# PowerBoard.net
KiCad netlist of a schematic drawn in EAGLE
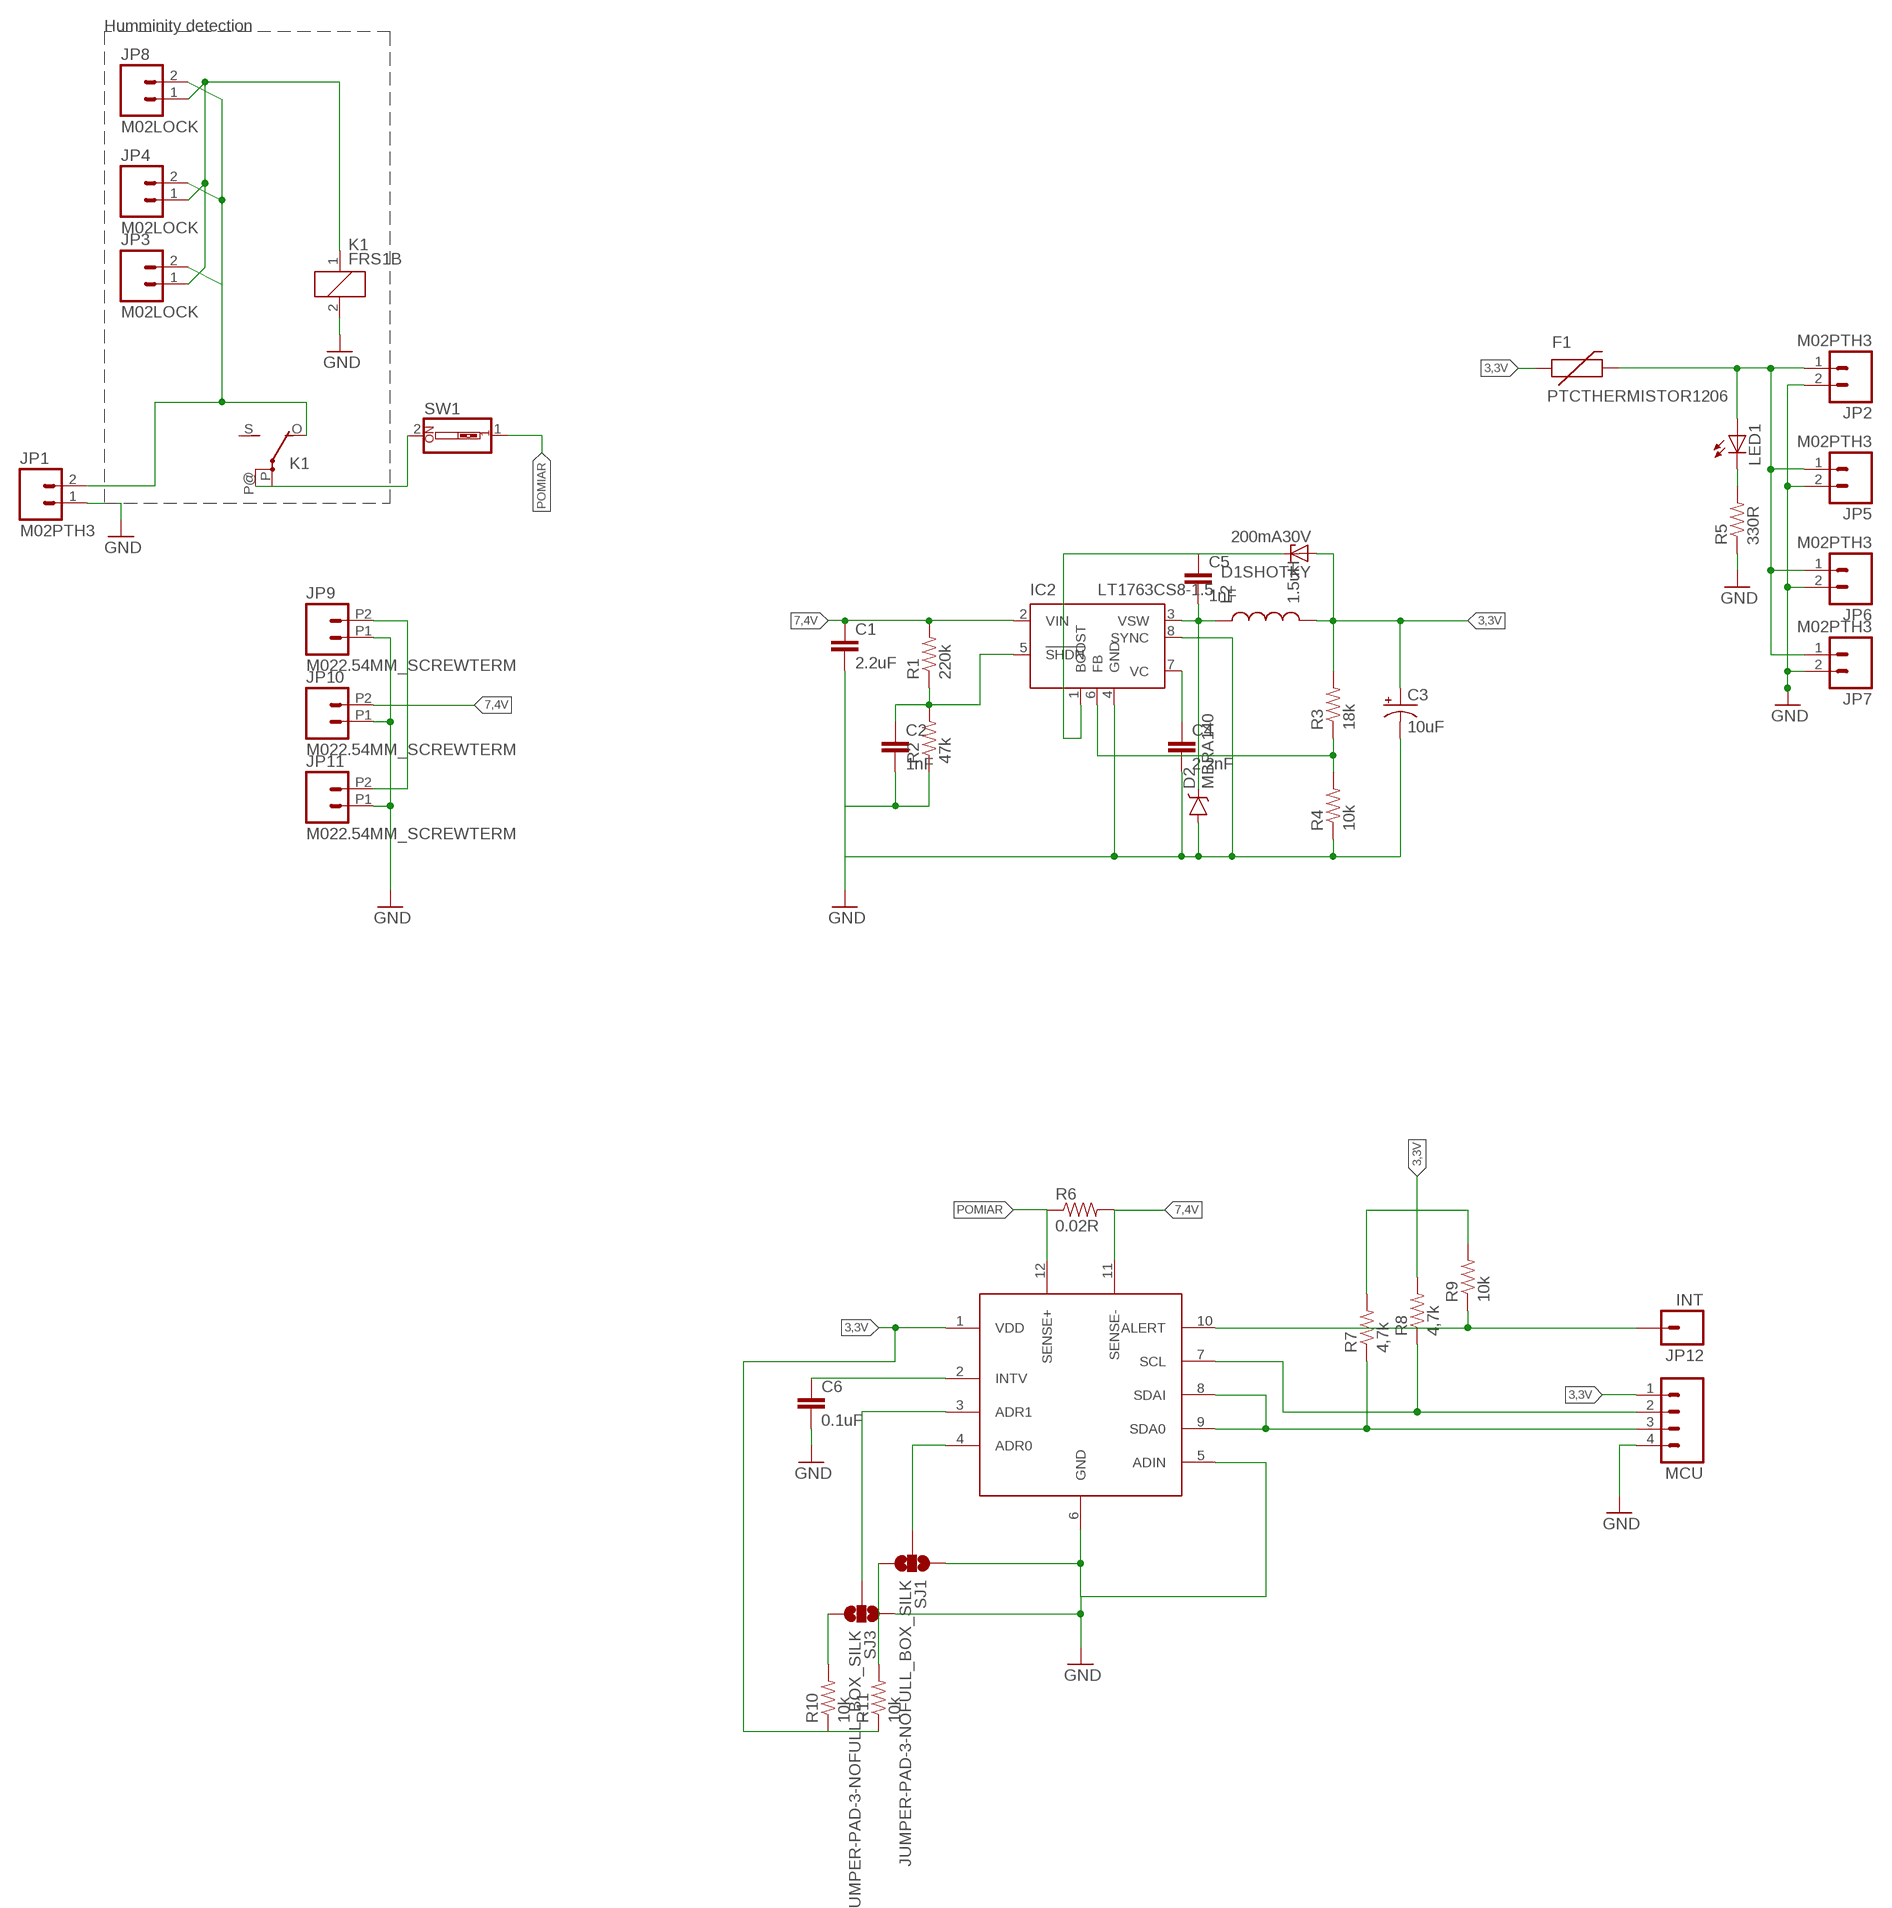
[diagram p0: schematic, sheet 1]

(export (version "E")
  (design (tool "Eeschema 10.0.6"))
  (components
    (comp (ref "C1")
      (value "2.2uF")
      (footprint "eagle-import:0805")
      (libsource (lib "eagle-import") (part "CAP0805"))
    )
    (comp (ref "C2")
      (value "1nF")
      (footprint "eagle-import:0805")
      (libsource (lib "eagle-import") (part "CAP0805"))
    )
    (comp (ref "C3")
      (value "10uF")
      (footprint "eagle-import:PANASONIC_C")
      (libsource (lib "eagle-import") (part "CAP_POLC"))
    )
    (comp (ref "C4")
      (value "2.2nF")
      (footprint "eagle-import:0805")
      (libsource (lib "eagle-import") (part "CAP0805"))
    )
    (comp (ref "C5")
      (value "1nF")
      (footprint "eagle-import:0805")
      (libsource (lib "eagle-import") (part "CAP0805"))
    )
    (comp (ref "C6")
      (value "0.1uF")
      (footprint "eagle-import:0805")
      (libsource (lib "eagle-import") (part "CAP0805"))
    )
    (comp (ref "D1SHOTKY")
      (value "200mA30V")
      (footprint "eagle-import:SOD80C")
      (libsource (lib "eagle-import") (part "ZENER-DIODESOD80C"))
    )
    (comp (ref "D2")
      (value "MBRA140")
      (footprint "eagle-import:SMA-DIODE")
      (libsource (lib "eagle-import") (part "MBRA140"))
    )
    (comp (ref "F1")
      (value "PTCTHERMISTOR1206")
      (footprint "eagle-import:PTC-1206")
      (libsource (lib "eagle-import") (part "PTCTHERMISTOR1206"))
    )
    (comp (ref "IC2")
      (value "LT1763CS8-1.5")
      (footprint "eagle-import:SOIC8")
      (libsource (lib "eagle-import") (part "LT1763CS8-1.5"))
    )
    (comp (ref "JP1")
      (value "M02PTH3")
      (footprint "eagle-import:1X02_LONGPADS")
      (libsource (lib "eagle-import") (part "M02PTH3"))
    )
    (comp (ref "JP2")
      (value "M02PTH3")
      (footprint "eagle-import:1X02_LONGPADS")
      (libsource (lib "eagle-import") (part "M02PTH3"))
    )
    (comp (ref "JP3")
      (value "M02LOCK")
      (footprint "eagle-import:1X02_LOCK")
      (libsource (lib "eagle-import") (part "M02LOCK"))
    )
    (comp (ref "JP4")
      (value "M02LOCK")
      (footprint "eagle-import:1X02_LOCK")
      (libsource (lib "eagle-import") (part "M02LOCK"))
    )
    (comp (ref "JP5")
      (value "M02PTH3")
      (footprint "eagle-import:1X02_LONGPADS")
      (libsource (lib "eagle-import") (part "M02PTH3"))
    )
    (comp (ref "JP6")
      (value "M02PTH3")
      (footprint "eagle-import:1X02_LONGPADS")
      (libsource (lib "eagle-import") (part "M02PTH3"))
    )
    (comp (ref "JP7")
      (value "M02PTH3")
      (footprint "eagle-import:1X02_LONGPADS")
      (libsource (lib "eagle-import") (part "M02PTH3"))
    )
    (comp (ref "JP8")
      (value "M02LOCK")
      (footprint "eagle-import:1X02_LOCK")
      (libsource (lib "eagle-import") (part "M02LOCK"))
    )
    (comp (ref "JP9")
      (value "M022.54MM_SCREWTERM")
      (footprint "eagle-import:1X02_2.54_SCREWTERM")
      (libsource (lib "eagle-import") (part "M022.54MM_SCREWTERM"))
    )
    (comp (ref "JP10")
      (value "M022.54MM_SCREWTERM")
      (footprint "eagle-import:1X02_2.54_SCREWTERM")
      (libsource (lib "eagle-import") (part "M022.54MM_SCREWTERM"))
    )
    (comp (ref "JP11")
      (value "M022.54MM_SCREWTERM")
      (footprint "eagle-import:1X02_2.54_SCREWTERM")
      (libsource (lib "eagle-import") (part "M022.54MM_SCREWTERM"))
    )
    (comp (ref "JP12")
      (value "INT")
      (footprint "eagle-import:1X01_LONGPAD")
      (libsource (lib "eagle-import") (part "M01PTH_LONGPAD"))
    )
    (comp (ref "K1")
      (value "FRS1B")
      (footprint "eagle-import:FRS1B")
      (libsource (lib "eagle-import") (part "FRS1B"))
    )
    (comp (ref "L2")
      (value "1.5uH")
      (footprint "eagle-import:B82462G")
      (libsource (lib "eagle-import") (part "INDUCTOR-B82462G"))
    )
    (comp (ref "LED1")
      (value "LEDSML0805")
      (footprint "eagle-import:SML0805")
      (libsource (lib "eagle-import") (part "LEDSML0805"))
    )
    (comp (ref "MCU")
      (value "M04POLAR_LOCK")
      (footprint "eagle-import:MOLEX-1X4_LOCK")
      (libsource (lib "eagle-import") (part "M04POLAR_LOCK"))
    )
    (comp (ref "R1")
      (value "220k")
      (footprint "eagle-import:0805")
      (libsource (lib "eagle-import") (part "SparkFun-Resistors_RESISTOR0805-RES"))
    )
    (comp (ref "R2")
      (value "47k")
      (footprint "eagle-import:0805")
      (libsource (lib "eagle-import") (part "SparkFun-Resistors_RESISTOR0805-RES"))
    )
    (comp (ref "R3")
      (value "18k")
      (footprint "eagle-import:0805")
      (libsource (lib "eagle-import") (part "SparkFun-Resistors_RESISTOR0805-RES"))
    )
    (comp (ref "R4")
      (value "10k")
      (footprint "eagle-import:0805")
      (libsource (lib "eagle-import") (part "SparkFun-Resistors_RESISTOR0805-RES"))
    )
    (comp (ref "R5")
      (value "330R")
      (footprint "eagle-import:0805")
      (libsource (lib "eagle-import") (part "SparkFun-Resistors_RESISTOR0805-RES"))
    )
    (comp (ref "R6")
      (value "0.02R")
      (footprint "eagle-import:R2512")
      (libsource (lib "eagle-import") (part "RESISTOR2512"))
    )
    (comp (ref "R7")
      (value "4,7k")
      (footprint "eagle-import:0805")
      (libsource (lib "eagle-import") (part "SparkFun-Resistors_RESISTOR0805-RES"))
    )
    (comp (ref "R8")
      (value "4,7k")
      (footprint "eagle-import:0805")
      (libsource (lib "eagle-import") (part "SparkFun-Resistors_RESISTOR0805-RES"))
    )
    (comp (ref "R9")
      (value "10k")
      (footprint "eagle-import:0805")
      (libsource (lib "eagle-import") (part "SparkFun-Resistors_RESISTOR0805-RES"))
    )
    (comp (ref "R10")
      (value "10k")
      (footprint "eagle-import:0805")
      (libsource (lib "eagle-import") (part "SparkFun-Resistors_RESISTOR0805-RES"))
    )
    (comp (ref "R11")
      (value "10k")
      (footprint "eagle-import:0805")
      (libsource (lib "eagle-import") (part "SparkFun-Resistors_RESISTOR0805-RES"))
    )
    (comp (ref "SJ1")
      (value "JUMPER-PAD-3-NOFULL_BOX_SILK")
      (footprint "eagle-import:PAD-JUMPER-3-NO_YES_SILK_FULL_BOX")
      (libsource (lib "eagle-import") (part "JUMPER-PAD-3-NOFULL_BOX_SILK"))
    )
    (comp (ref "SJ3")
      (value "JUMPER-PAD-3-NOFULL_BOX_SILK")
      (footprint "eagle-import:PAD-JUMPER-3-NO_YES_SILK_FULL_BOX")
      (libsource (lib "eagle-import") (part "JUMPER-PAD-3-NOFULL_BOX_SILK"))
    )
    (comp (ref "SW1")
      (value "SW_DIP-1")
      (footprint "eagle-import:EDG-01")
      (libsource (lib "eagle-import") (part "SW_DIP-1"))
    )
    (comp (ref "U$1")
      (value "LTC2945")
      (footprint "eagle-import:SOP65P490X110-12N")
      (libsource (lib "eagle-import") (part "LTC2945"))
    )
  )
  (nets
    (net (code "1") (name "3,3V") (class "Default")
      (node (ref "C3") (pin "+") (pinfunction "+_+") (pintype "passive"))
      (node (ref "D1SHOTKY") (pin "A") (pinfunction "A_A") (pintype "passive"))
      (node (ref "F1") (pin "1") (pinfunction "1_1") (pintype "bidirectional"))
      (node (ref "L2") (pin "P$2") (pinfunction "2_P$2") (pintype "passive"))
      (node (ref "MCU") (pin "1") (pinfunction "1_1") (pintype "passive"))
      (node (ref "R10") (pin "1") (pinfunction "1_1") (pintype "passive"))
      (node (ref "R11") (pin "1") (pinfunction "1_1") (pintype "passive"))
      (node (ref "R3") (pin "2") (pinfunction "2_2") (pintype "passive"))
      (node (ref "R7") (pin "2") (pinfunction "2_2") (pintype "passive"))
      (node (ref "R8") (pin "2") (pinfunction "2_2") (pintype "passive"))
      (node (ref "R9") (pin "2") (pinfunction "2_2") (pintype "passive"))
      (node (ref "U$1") (pin "1") (pinfunction "VDD_1") (pintype "bidirectional"))
    )
    (net (code "2") (name "7,4V") (class "Default")
      (node (ref "C1") (pin "1") (pinfunction "1_1") (pintype "passive"))
      (node (ref "IC2") (pin "2") (pinfunction "VIN_2") (pintype "input"))
      (node (ref "JP10") (pin "P2") (pinfunction "2_P2") (pintype "passive"))
      (node (ref "JP11") (pin "P2") (pinfunction "2_P2") (pintype "passive"))
      (node (ref "JP9") (pin "P2") (pinfunction "2_P2") (pintype "passive"))
      (node (ref "R1") (pin "2") (pinfunction "2_2") (pintype "passive"))
      (node (ref "R6") (pin "2") (pinfunction "2_2") (pintype "passive"))
      (node (ref "U$1") (pin "11") (pinfunction "SENSE-_11") (pintype "bidirectional"))
    )
    (net (code "3") (name "GND") (class "Default")
      (node (ref "C1") (pin "2") (pinfunction "2_2") (pintype "passive"))
      (node (ref "C2") (pin "2") (pinfunction "2_2") (pintype "passive"))
      (node (ref "C3") (pin "-") (pinfunction "-_-") (pintype "passive"))
      (node (ref "C4") (pin "2") (pinfunction "2_2") (pintype "passive"))
      (node (ref "C6") (pin "2") (pinfunction "2_2") (pintype "passive"))
      (node (ref "D2") (pin "A") (pinfunction "A_A") (pintype "passive"))
      (node (ref "IC2") (pin "4") (pinfunction "GND_4") (pintype "power_in"))
      (node (ref "IC2") (pin "8") (pinfunction "SYNC_8") (pintype "input"))
      (node (ref "JP1") (pin "1") (pinfunction "1_1") (pintype "passive"))
      (node (ref "JP10") (pin "P1") (pinfunction "1_P1") (pintype "passive"))
      (node (ref "JP11") (pin "P1") (pinfunction "1_P1") (pintype "passive"))
      (node (ref "JP2") (pin "2") (pinfunction "2_2") (pintype "passive"))
      (node (ref "JP5") (pin "2") (pinfunction "2_2") (pintype "passive"))
      (node (ref "JP6") (pin "2") (pinfunction "2_2") (pintype "passive"))
      (node (ref "JP7") (pin "2") (pinfunction "2_2") (pintype "passive"))
      (node (ref "JP9") (pin "P1") (pinfunction "1_P1") (pintype "passive"))
      (node (ref "K1") (pin "2") (pinfunction "2_2") (pintype "passive"))
      (node (ref "MCU") (pin "4") (pinfunction "4_4") (pintype "passive"))
      (node (ref "R2") (pin "1") (pinfunction "1_1") (pintype "passive"))
      (node (ref "R4") (pin "1") (pinfunction "1_1") (pintype "passive"))
      (node (ref "R5") (pin "1") (pinfunction "1_1") (pintype "passive"))
      (node (ref "SJ1") (pin "1") (pinfunction "1_1") (pintype "passive"))
      (node (ref "SJ3") (pin "1") (pinfunction "1_1") (pintype "passive"))
      (node (ref "U$1") (pin "5") (pinfunction "ADIN_5") (pintype "bidirectional"))
      (node (ref "U$1") (pin "6") (pinfunction "GND_6") (pintype "bidirectional"))
    )
    (net (code "4") (name "Net-(F1-Pad2)") (class "Default")
      (node (ref "F1") (pin "2") (pinfunction "2_2") (pintype "bidirectional"))
      (node (ref "JP2") (pin "1") (pinfunction "1_1") (pintype "passive"))
      (node (ref "JP5") (pin "1") (pinfunction "1_1") (pintype "passive"))
      (node (ref "JP6") (pin "1") (pinfunction "1_1") (pintype "passive"))
      (node (ref "JP7") (pin "1") (pinfunction "1_1") (pintype "passive"))
      (node (ref "LED1") (pin "A") (pinfunction "A_A") (pintype "passive"))
    )
    (net (code "5") (name "Net-(IC2-BOOST)") (class "Default")
      (node (ref "C5") (pin "1") (pinfunction "1_1") (pintype "passive"))
      (node (ref "D1SHOTKY") (pin "C") (pinfunction "C_C") (pintype "passive"))
      (node (ref "IC2") (pin "1") (pinfunction "BOOST_1") (pintype "power_in"))
    )
    (net (code "6") (name "Net-(IC2-FB)") (class "Default")
      (node (ref "IC2") (pin "6") (pinfunction "FB_6") (pintype "power_in"))
      (node (ref "R3") (pin "1") (pinfunction "1_1") (pintype "passive"))
      (node (ref "R4") (pin "2") (pinfunction "2_2") (pintype "passive"))
    )
    (net (code "7") (name "Net-(IC2-VC)") (class "Default")
      (node (ref "C4") (pin "1") (pinfunction "1_1") (pintype "passive"))
      (node (ref "IC2") (pin "7") (pinfunction "VC_7") (pintype "input"))
    )
    (net (code "8") (name "Net-(IC2-VSW)") (class "Default")
      (node (ref "C5") (pin "2") (pinfunction "2_2") (pintype "passive"))
      (node (ref "D2") (pin "C") (pinfunction "C_C") (pintype "passive"))
      (node (ref "IC2") (pin "3") (pinfunction "VSW_3") (pintype "passive"))
      (node (ref "L2") (pin "P$1") (pinfunction "1_P$1") (pintype "passive"))
    )
    (net (code "9") (name "Net-(IC2-~{SHDN})") (class "Default")
      (node (ref "C2") (pin "1") (pinfunction "1_1") (pintype "passive"))
      (node (ref "IC2") (pin "5") (pinfunction "~{SHDN}_5") (pintype "input"))
      (node (ref "R1") (pin "1") (pinfunction "1_1") (pintype "passive"))
      (node (ref "R2") (pin "2") (pinfunction "2_2") (pintype "passive"))
    )
    (net (code "10") (name "Net-(JP1-Pad2)") (class "Default")
      (node (ref "JP1") (pin "2") (pinfunction "2_2") (pintype "passive"))
      (node (ref "JP3") (pin "2") (pinfunction "2_2") (pintype "passive"))
      (node (ref "JP4") (pin "2") (pinfunction "2_2") (pintype "passive"))
      (node (ref "JP8") (pin "2") (pinfunction "2_2") (pintype "passive"))
      (node (ref "K1") (pin "O") (pinfunction "O_O") (pintype "passive"))
    )
    (net (code "11") (name "Net-(JP3-Pad1)") (class "Default")
      (node (ref "JP3") (pin "1") (pinfunction "1_1") (pintype "passive"))
      (node (ref "JP4") (pin "1") (pinfunction "1_1") (pintype "passive"))
      (node (ref "JP8") (pin "1") (pinfunction "1_1") (pintype "passive"))
      (node (ref "K1") (pin "1") (pinfunction "1_1") (pintype "passive"))
    )
    (net (code "12") (name "Net-(K1-PadP)") (class "Default")
      (node (ref "K1") (pin "P") (pinfunction "P_P") (pintype "passive"))
      (node (ref "K1") (pin "P@") (pinfunction "P_P@") (pintype "passive"))
      (node (ref "SW1") (pin "2") (pinfunction "2_2") (pintype "passive"))
    )
    (net (code "13") (name "Net-(LED1-PadC)") (class "Default")
      (node (ref "LED1") (pin "C") (pinfunction "C_C") (pintype "passive"))
      (node (ref "R5") (pin "2") (pinfunction "2_2") (pintype "passive"))
    )
    (net (code "14") (name "Net-(R10-Pad2)") (class "Default")
      (node (ref "R10") (pin "2") (pinfunction "2_2") (pintype "passive"))
      (node (ref "SJ3") (pin "3") (pinfunction "3_3") (pintype "passive"))
    )
    (net (code "15") (name "Net-(R11-Pad2)") (class "Default")
      (node (ref "R11") (pin "2") (pinfunction "2_2") (pintype "passive"))
      (node (ref "SJ1") (pin "3") (pinfunction "3_3") (pintype "passive"))
    )
    (net (code "16") (name "Net-(U$1-ADR0)") (class "Default")
      (node (ref "SJ1") (pin "2") (pinfunction "2_2") (pintype "passive"))
      (node (ref "U$1") (pin "4") (pinfunction "ADR0_4") (pintype "bidirectional"))
    )
    (net (code "17") (name "Net-(U$1-ADR1)") (class "Default")
      (node (ref "SJ3") (pin "2") (pinfunction "2_2") (pintype "passive"))
      (node (ref "U$1") (pin "3") (pinfunction "ADR1_3") (pintype "bidirectional"))
    )
    (net (code "18") (name "Net-(U$1-ALERT)") (class "Default")
      (node (ref "JP12") (pin "1") (pinfunction "1_1") (pintype "passive"))
      (node (ref "R9") (pin "1") (pinfunction "1_1") (pintype "passive"))
      (node (ref "U$1") (pin "10") (pinfunction "ALERT_10") (pintype "bidirectional"))
    )
    (net (code "19") (name "Net-(U$1-INTV)") (class "Default")
      (node (ref "C6") (pin "1") (pinfunction "1_1") (pintype "passive"))
      (node (ref "U$1") (pin "2") (pinfunction "INTV_2") (pintype "bidirectional"))
    )
    (net (code "20") (name "Net-(U$1-SCL)") (class "Default")
      (node (ref "MCU") (pin "2") (pinfunction "2_2") (pintype "passive"))
      (node (ref "R8") (pin "1") (pinfunction "1_1") (pintype "passive"))
      (node (ref "U$1") (pin "7") (pinfunction "SCL_7") (pintype "bidirectional"))
    )
    (net (code "21") (name "Net-(U$1-SDA0)") (class "Default")
      (node (ref "MCU") (pin "3") (pinfunction "3_3") (pintype "passive"))
      (node (ref "R7") (pin "1") (pinfunction "1_1") (pintype "passive"))
      (node (ref "U$1") (pin "8") (pinfunction "SDAI_8") (pintype "bidirectional"))
      (node (ref "U$1") (pin "9") (pinfunction "SDA0_9") (pintype "bidirectional"))
    )
    (net (code "22") (name "POMIAR") (class "Default")
      (node (ref "R6") (pin "1") (pinfunction "1_1") (pintype "passive"))
      (node (ref "SW1") (pin "1") (pinfunction "1_1") (pintype "passive"))
      (node (ref "U$1") (pin "12") (pinfunction "SENSE+_12") (pintype "bidirectional"))
    )
    (net (code "23") (name "unconnected-(K1-PadS)") (class "Default")
      (node (ref "K1") (pin "S") (pinfunction "S_S") (pintype "passive"))
    )
  )
)
